# ministm32.net
KiCad netlist of a schematic drawn in EasyEDA Pro
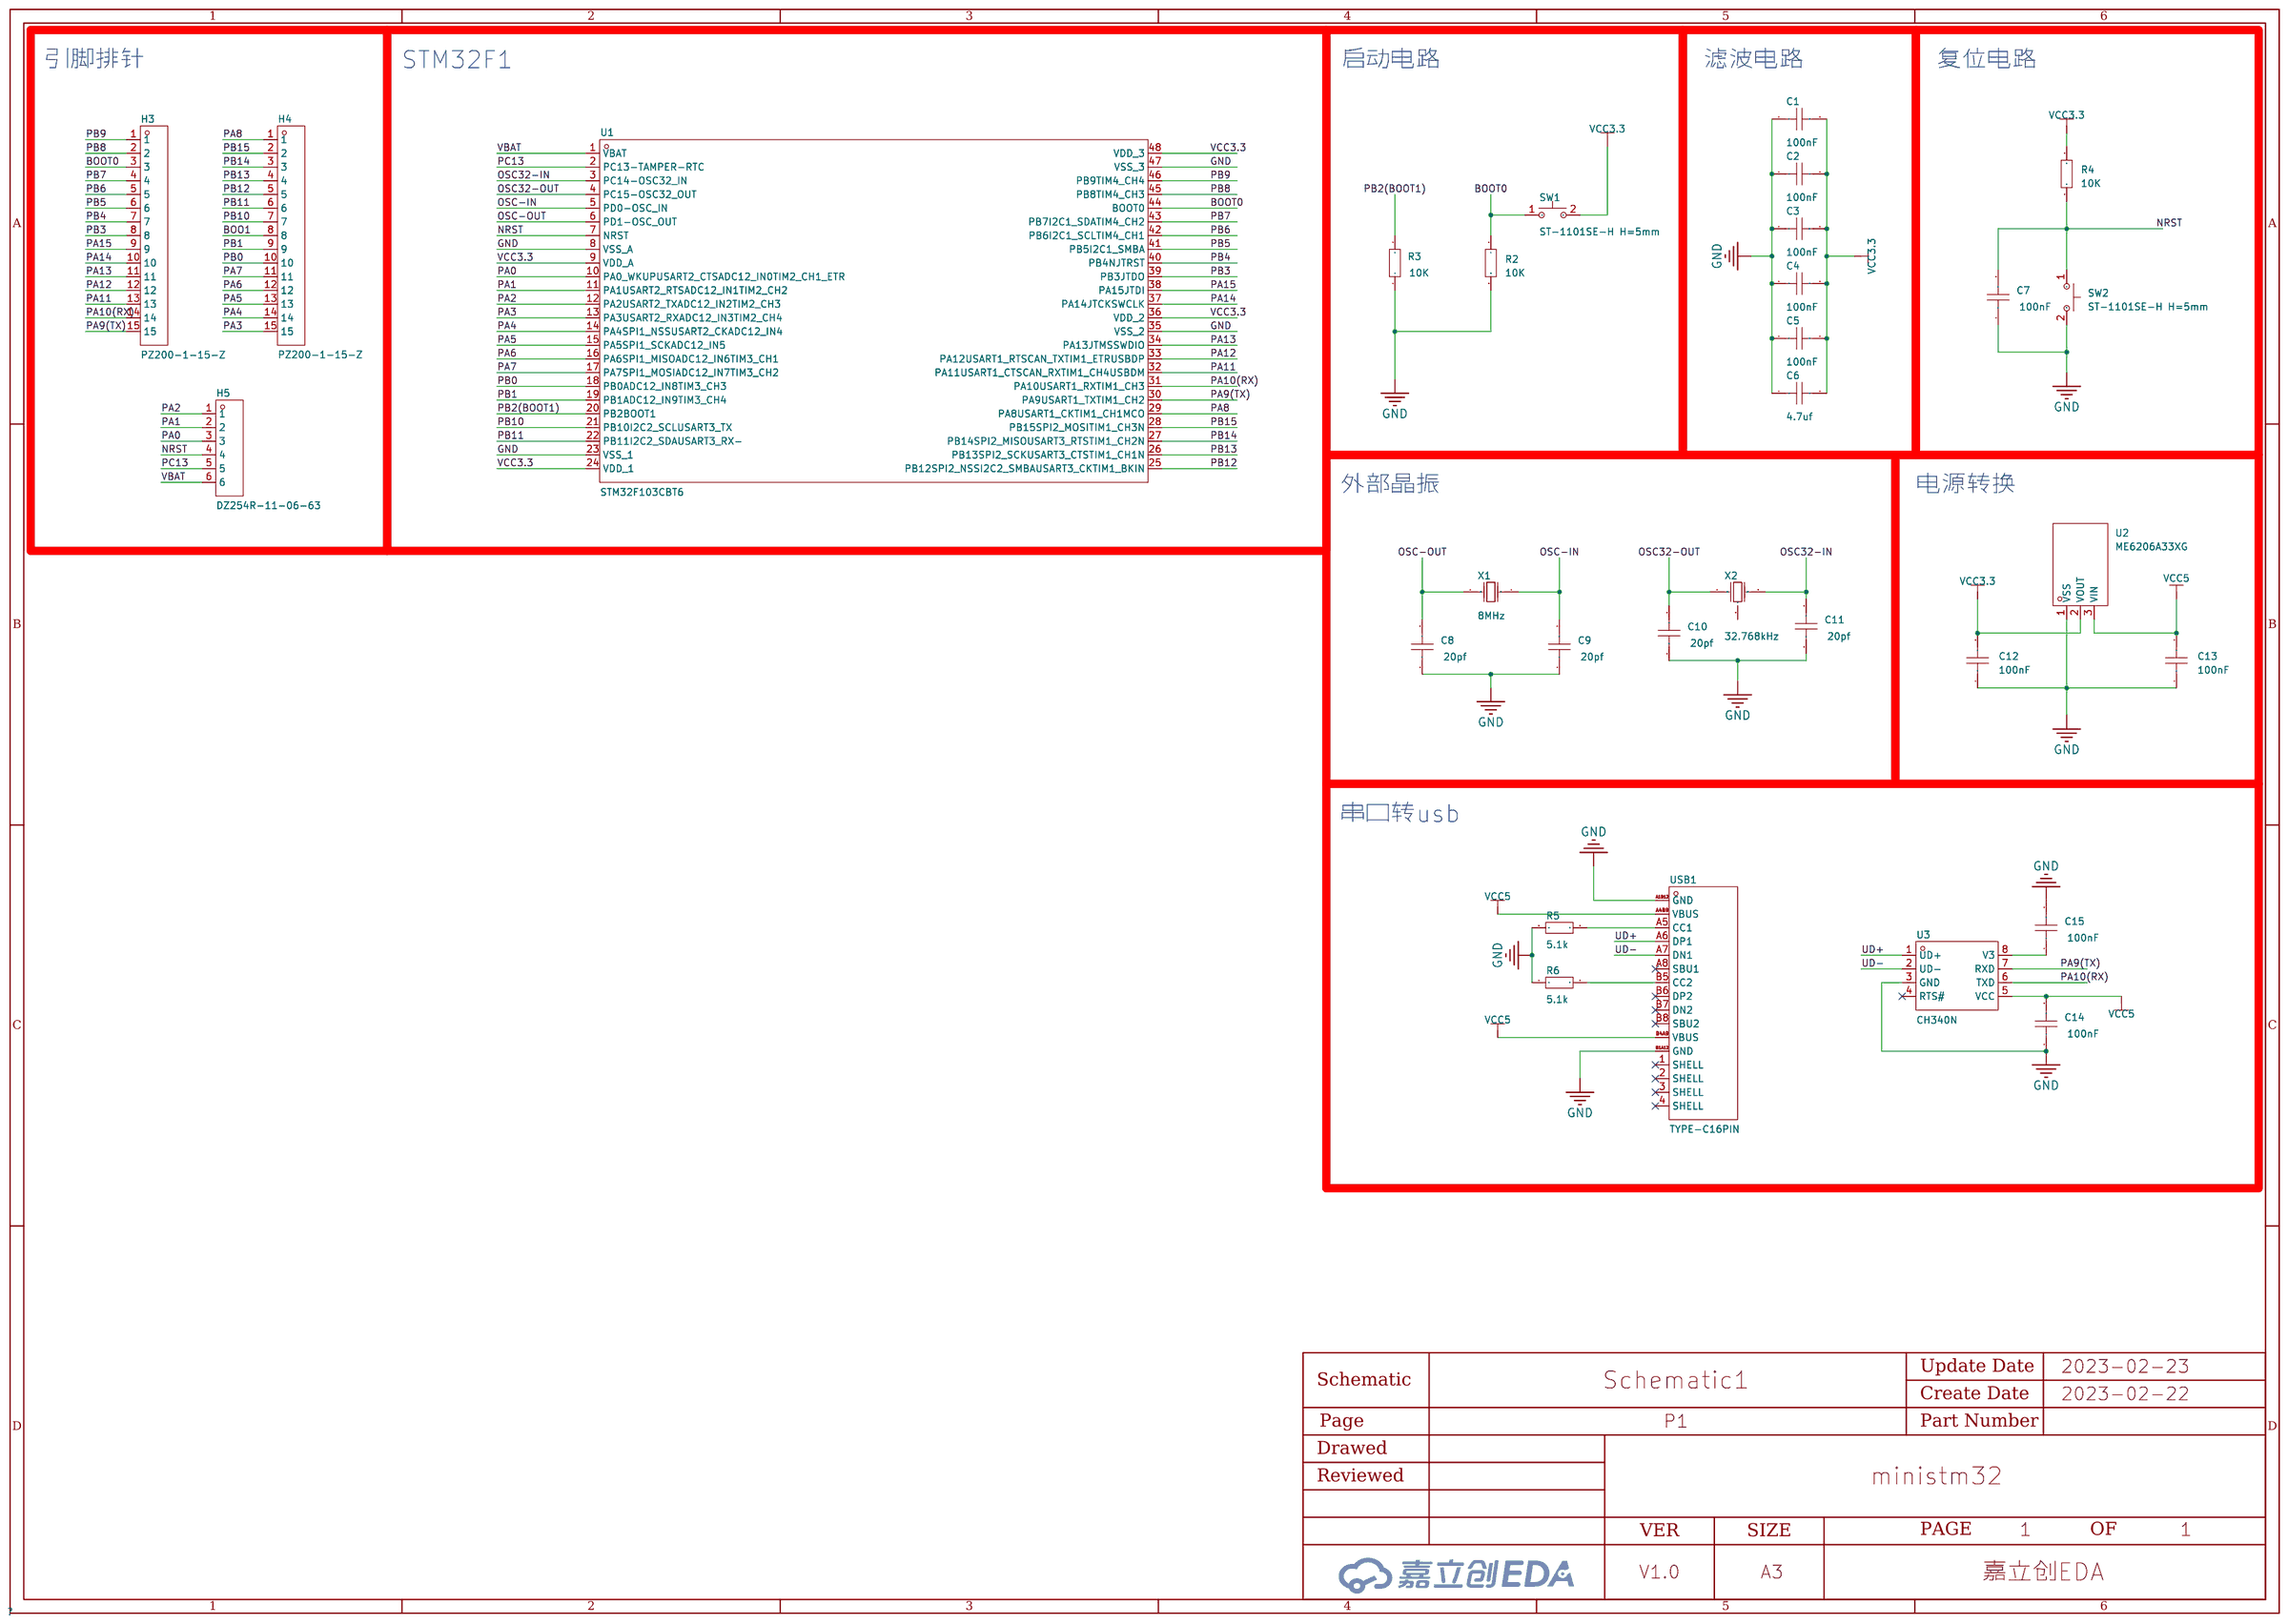
[diagram p0: schematic sheet]

(export (version "E")
  (design (tool "Eeschema 10.0.6"))
  (components
    (comp (ref "C1")
      (value "100nF")
      (footprint "easyedapro:C0603")
      (libsource (lib "easyedapro") (part "CapAcitance"))
    )
    (comp (ref "C2")
      (value "100nF")
      (footprint "easyedapro:C0603")
      (libsource (lib "easyedapro") (part "CapAcitance"))
    )
    (comp (ref "C3")
      (value "100nF")
      (footprint "easyedapro:C0603")
      (libsource (lib "easyedapro") (part "CapAcitance"))
    )
    (comp (ref "C4")
      (value "100nF")
      (footprint "easyedapro:C0603")
      (libsource (lib "easyedapro") (part "CapAcitance"))
    )
    (comp (ref "C5")
      (value "100nF")
      (footprint "easyedapro:C0603")
      (libsource (lib "easyedapro") (part "CapAcitance"))
    )
    (comp (ref "C6")
      (value "4.7uf")
      (footprint "easyedapro:C0603")
      (libsource (lib "easyedapro") (part "CapAcitance"))
    )
    (comp (ref "C7")
      (value "100nF")
      (footprint "easyedapro:C0603")
      (libsource (lib "easyedapro") (part "CapAcitance"))
    )
    (comp (ref "C8")
      (value "20pf")
      (footprint "easyedapro:C0603")
      (libsource (lib "easyedapro") (part "CapAcitance"))
    )
    (comp (ref "C9")
      (value "20pf")
      (footprint "easyedapro:C0603")
      (libsource (lib "easyedapro") (part "CapAcitance"))
    )
    (comp (ref "C10")
      (value "20pf")
      (footprint "easyedapro:C0603")
      (libsource (lib "easyedapro") (part "CapAcitance"))
    )
    (comp (ref "C11")
      (value "20pf")
      (footprint "easyedapro:C0603")
      (libsource (lib "easyedapro") (part "CapAcitance"))
    )
    (comp (ref "C12")
      (value "100nF")
      (footprint "easyedapro:C0603")
      (libsource (lib "easyedapro") (part "CapAcitance"))
    )
    (comp (ref "C13")
      (value "100nF")
      (footprint "easyedapro:C0603")
      (libsource (lib "easyedapro") (part "CapAcitance"))
    )
    (comp (ref "C14")
      (value "100nF")
      (footprint "easyedapro:C0603")
      (libsource (lib "easyedapro") (part "CapAcitance"))
    )
    (comp (ref "C15")
      (value "100nF")
      (footprint "easyedapro:C0603")
      (libsource (lib "easyedapro") (part "CapAcitance"))
    )
    (comp (ref "H3")
      (value "PZ200-1-15-Z")
      (footprint "easyedapro:HDR-TH_15P-P2.00-V-M")
      (fields (field (name "Manufacturer") "HCTL(华灿天禄)"))
      (libsource (lib "easyedapro") (part "PZ200-1-15-Z"))
    )
    (comp (ref "H4")
      (value "PZ200-1-15-Z")
      (footprint "easyedapro:HDR-TH_15P-P2.00-V-M")
      (fields (field (name "Manufacturer") "HCTL(华灿天禄)"))
      (libsource (lib "easyedapro") (part "PZ200-1-15-Z"))
    )
    (comp (ref "H5")
      (value "DZ254R-11-06-63")
      (footprint "easyedapro:HDR-TH_6P-P2.54-V-M")
      (fields (field (name "Manufacturer") "DEALON(德艺隆)"))
      (libsource (lib "easyedapro") (part "DZ254R-11-06-63"))
    )
    (comp (ref "R2") (value "10K") (footprint "easyedapro:R0603") (libsource (lib "easyedapro") (part "电阻")))
    (comp (ref "R3") (value "10K") (footprint "easyedapro:R0603") (libsource (lib "easyedapro") (part "电阻")))
    (comp (ref "R4") (value "10K") (footprint "easyedapro:R0603") (libsource (lib "easyedapro") (part "电阻")))
    (comp (ref "R5") (value "5.1k") (footprint "easyedapro:R0603") (libsource (lib "easyedapro") (part "电阻")))
    (comp (ref "R6") (value "5.1k") (footprint "easyedapro:R0603") (libsource (lib "easyedapro") (part "电阻")))
    (comp (ref "SW1")
      (value "ST-1101SE-H H=5mm")
      (footprint "easyedapro:SW-SMD_L6.1-W3.6-LS8.3-EH")
      (fields (field (name "Manufacturer") "RISHENG(日昇)"))
      (libsource (lib "easyedapro") (part "ST-1101SE-H H=5MM"))
    )
    (comp (ref "SW2")
      (value "ST-1101SE-H H=5mm")
      (footprint "easyedapro:SW-SMD_L6.1-W3.6-LS8.3-EH")
      (fields (field (name "Manufacturer") "RISHENG(日昇)"))
      (libsource (lib "easyedapro") (part "ST-1101SE-H H=5MM"))
    )
    (comp (ref "U1")
      (value "STM32F103CBT6")
      (footprint "easyedapro:LQFP-48_L7.0-W7.0-P0.50-LS9.0-BL")
      (fields (field (name "Manufacturer") "ST(意法半导体)"))
      (libsource (lib "easyedapro") (part "STM32F103CBT6"))
    )
    (comp (ref "U2")
      (value "ME6206A33XG")
      (footprint "easyedapro:SOT-23-3_L2.9-W1.6-P1.90-LS2.8-BR")
      (description "输出类型:固定;输出极性:正;输出通道数:1;最大输入电压:6V;输出电压:3.3V;压差:400mV@(200mA);输出电流:300mA;电源纹波抑制比(PSRR):50dB@(1kHz);")
      (fields (field (name "Manufacturer") "MICRONE(南京微盟)"))
      (libsource (lib "easyedapro") (part "ME6206A33XG"))
    )
    (comp (ref "U3")
      (value "CH340N")
      (footprint "easyedapro:SOP-8_L4.9-W3.9-P1.27-LS6.0-BL")
      (fields (field (name "Manufacturer") "WCH(南京沁恒)"))
      (libsource (lib "easyedapro") (part "CH340N_C2977777"))
    )
    (comp (ref "USB1")
      (value "TYPE-C16PIN")
      (footprint "easyedapro:USB-C-SMD_TYPE-C16PIN")
      (description "连接器类型:Type-C;标准:-;公母:母座;触点数量:16;端口数量:1;安装方式:卧贴;额定电流 - 电源:3A;工作温度范围:-40°C~+85°C;")
      (fields (field (name "Manufacturer") "SHOU HAN(首韩)"))
      (libsource (lib "easyedapro") (part "TYPE-C16PIN"))
    )
    (comp (ref "X1")
      (value "8MHz")
      (footprint "easyedapro:CRYSTAL-SMD_L11.5-W4.8-LS12.7")
      (description "晶振类型:49SMD;频率:8MHz;频率公差:±20ppm;频率稳定度:±30ppm;负载电容:20pF;工作温度:-20°C~+70°C;")
      (fields (field (name "Manufacturer Part") "X49SM8MSD2SC") (field (name "Manufacturer") "YXC(扬兴晶振)"))
      (libsource (lib "easyedapro") (part "X49SM8MSD2SC"))
    )
    (comp (ref "X2")
      (value "32.768kHz")
      (footprint "easyedapro:OSC-SMD_BD2.0-P2.54_TMXLI-206F32.768KHZ12.5PF20PPM")
      (description "晶振类型:贴片无源晶振;频率:32.768kHz;频率公差:±10ppm;负载电容:12.5pF;工作温度:-;")
      (fields
        (field (name "Manufacturer Part") "TAXM32768KBGBAZN2T")
        (field (name "Manufacturer") "TAE(雅晶鑫)")
      )
      (libsource (lib "easyedapro") (part "TMXLI-206F32.768KHZ12PF10PPM"))
    )
  )
  (nets
    (net (code "1") (name "/BOO1") (class "Default")
      (node (ref "H4") (pin "8") (pinfunction "8_8") (pintype "input"))
    )
    (net (code "2") (name "/BOOT0") (class "Default")
      (node (ref "H3") (pin "3") (pinfunction "3_3") (pintype "input"))
      (node (ref "R2") (pin "1") (pinfunction "1_1") (pintype "input"))
      (node (ref "SW1") (pin "1") (pinfunction "1_1") (pintype "input"))
      (node (ref "U1") (pin "44") (pinfunction "BOOT0_44") (pintype "input"))
    )
    (net (code "3") (name "/NRST") (class "Default")
      (node (ref "C7") (pin "2") (pinfunction "2_2") (pintype "input"))
      (node (ref "H5") (pin "4") (pinfunction "4_4") (pintype "input"))
      (node (ref "R4") (pin "1") (pinfunction "1_1") (pintype "input"))
      (node (ref "SW2") (pin "1") (pinfunction "1_1") (pintype "input"))
      (node (ref "U1") (pin "7") (pinfunction "NRST_7") (pintype "input"))
    )
    (net (code "4") (name "/OSC-IN") (class "Default")
      (node (ref "C9") (pin "2") (pinfunction "2_2") (pintype "input"))
      (node (ref "U1") (pin "5") (pinfunction "PD0-OSC_IN_5") (pintype "input"))
      (node (ref "X1") (pin "1") (pinfunction "OSC1_1") (pintype "input"))
    )
    (net (code "5") (name "/OSC-OUT") (class "Default")
      (node (ref "C8") (pin "2") (pinfunction "2_2") (pintype "input"))
      (node (ref "U1") (pin "6") (pinfunction "PD1-OSC_OUT_6") (pintype "input"))
      (node (ref "X1") (pin "2") (pinfunction "OSC2_2") (pintype "input"))
    )
    (net (code "6") (name "/OSC32-IN") (class "Default")
      (node (ref "C11") (pin "2") (pinfunction "2_2") (pintype "input"))
      (node (ref "U1") (pin "3") (pinfunction "PC14-OSC32_IN_3") (pintype "input"))
      (node (ref "X2") (pin "2") (pinfunction "OSC2_2") (pintype "input"))
    )
    (net (code "7") (name "/OSC32-OUT") (class "Default")
      (node (ref "C10") (pin "2") (pinfunction "2_2") (pintype "input"))
      (node (ref "U1") (pin "4") (pinfunction "PC15-OSC32_OUT_4") (pintype "input"))
      (node (ref "X2") (pin "1") (pinfunction "OSC1_1") (pintype "input"))
    )
    (net (code "8") (name "/PA0") (class "Default")
      (node (ref "H5") (pin "3") (pinfunction "3_3") (pintype "input"))
      (node (ref "U1") (pin "10") (pinfunction "PA0_WKUPUSART2_CTSADC12_IN0TIM2_CH1_ETR_10") (pintype "input"))
    )
    (net (code "9") (name "/PA1") (class "Default")
      (node (ref "H5") (pin "2") (pinfunction "2_2") (pintype "input"))
      (node (ref "U1") (pin "11") (pinfunction "PA1USART2_RTSADC12_IN1TIM2_CH2_11") (pintype "input"))
    )
    (net (code "10") (name "/PA2") (class "Default")
      (node (ref "H5") (pin "1") (pinfunction "1_1") (pintype "input"))
      (node (ref "U1") (pin "12") (pinfunction "PA2USART2_TXADC12_IN2TIM2_CH3_12") (pintype "input"))
    )
    (net (code "11") (name "/PA3") (class "Default")
      (node (ref "H4") (pin "15") (pinfunction "15_15") (pintype "input"))
      (node (ref "U1") (pin "13") (pinfunction "PA3USART2_RXADC12_IN3TIM2_CH4_13") (pintype "input"))
    )
    (net (code "12") (name "/PA4") (class "Default")
      (node (ref "H4") (pin "14") (pinfunction "14_14") (pintype "input"))
      (node (ref "U1") (pin "14") (pinfunction "PA4SPI1_NSSUSART2_CKADC12_IN4_14") (pintype "input"))
    )
    (net (code "13") (name "/PA5") (class "Default")
      (node (ref "H4") (pin "13") (pinfunction "13_13") (pintype "input"))
      (node (ref "U1") (pin "15") (pinfunction "PA5SPI1_SCKADC12_IN5_15") (pintype "input"))
    )
    (net (code "14") (name "/PA6") (class "Default")
      (node (ref "H4") (pin "12") (pinfunction "12_12") (pintype "input"))
      (node (ref "U1") (pin "16") (pinfunction "PA6SPI1_MISOADC12_IN6TIM3_CH1_16") (pintype "input"))
    )
    (net (code "15") (name "/PA7") (class "Default")
      (node (ref "H4") (pin "11") (pinfunction "11_11") (pintype "input"))
      (node (ref "U1") (pin "17") (pinfunction "PA7SPI1_MOSIADC12_IN7TIM3_CH2_17") (pintype "input"))
    )
    (net (code "16") (name "/PA8") (class "Default")
      (node (ref "H4") (pin "1") (pinfunction "1_1") (pintype "input"))
      (node (ref "U1") (pin "29") (pinfunction "PA8USART1_CKTIM1_CH1MCO_29") (pintype "input"))
    )
    (net (code "17") (name "/PA9(TX)") (class "Default")
      (node (ref "H3") (pin "15") (pinfunction "15_15") (pintype "input"))
      (node (ref "U1") (pin "30") (pinfunction "PA9USART1_TXTIM1_CH2_30") (pintype "input"))
      (node (ref "U3") (pin "7") (pinfunction "RXD_7") (pintype "input"))
    )
    (net (code "18") (name "/PA10(RX)") (class "Default")
      (node (ref "H3") (pin "14") (pinfunction "14_14") (pintype "input"))
      (node (ref "U1") (pin "31") (pinfunction "PA10USART1_RXTIM1_CH3_31") (pintype "input"))
      (node (ref "U3") (pin "6") (pinfunction "TXD_6") (pintype "input"))
    )
    (net (code "19") (name "/PA11") (class "Default")
      (node (ref "H3") (pin "13") (pinfunction "13_13") (pintype "input"))
      (node (ref "U1") (pin "32") (pinfunction "PA11USART1_CTSCAN_RXTIM1_CH4USBDM_32") (pintype "input"))
    )
    (net (code "20") (name "/PA12") (class "Default")
      (node (ref "H3") (pin "12") (pinfunction "12_12") (pintype "input"))
      (node (ref "U1") (pin "33") (pinfunction "PA12USART1_RTSCAN_TXTIM1_ETRUSBDP_33") (pintype "input"))
    )
    (net (code "21") (name "/PA13") (class "Default")
      (node (ref "H3") (pin "11") (pinfunction "11_11") (pintype "input"))
      (node (ref "U1") (pin "34") (pinfunction "PA13JTMSSWDIO_34") (pintype "input"))
    )
    (net (code "22") (name "/PA14") (class "Default")
      (node (ref "H3") (pin "10") (pinfunction "10_10") (pintype "input"))
      (node (ref "U1") (pin "37") (pinfunction "PA14JTCKSWCLK_37") (pintype "input"))
    )
    (net (code "23") (name "/PA15") (class "Default")
      (node (ref "H3") (pin "9") (pinfunction "9_9") (pintype "input"))
      (node (ref "U1") (pin "38") (pinfunction "PA15JTDI_38") (pintype "input"))
    )
    (net (code "24") (name "/PB0") (class "Default")
      (node (ref "H4") (pin "10") (pinfunction "10_10") (pintype "input"))
      (node (ref "U1") (pin "18") (pinfunction "PB0ADC12_IN8TIM3_CH3_18") (pintype "input"))
    )
    (net (code "25") (name "/PB1") (class "Default")
      (node (ref "H4") (pin "9") (pinfunction "9_9") (pintype "input"))
      (node (ref "U1") (pin "19") (pinfunction "PB1ADC12_IN9TIM3_CH4_19") (pintype "input"))
    )
    (net (code "26") (name "/PB2(BOOT1)") (class "Default")
      (node (ref "R3") (pin "2") (pinfunction "2_2") (pintype "input"))
      (node (ref "U1") (pin "20") (pinfunction "PB2BOOT1_20") (pintype "input"))
    )
    (net (code "27") (name "/PB3") (class "Default")
      (node (ref "H3") (pin "8") (pinfunction "8_8") (pintype "input"))
      (node (ref "U1") (pin "39") (pinfunction "PB3JTDO_39") (pintype "input"))
    )
    (net (code "28") (name "/PB4") (class "Default")
      (node (ref "H3") (pin "7") (pinfunction "7_7") (pintype "input"))
      (node (ref "U1") (pin "40") (pinfunction "PB4NJTRST_40") (pintype "input"))
    )
    (net (code "29") (name "/PB5") (class "Default")
      (node (ref "H3") (pin "6") (pinfunction "6_6") (pintype "input"))
      (node (ref "U1") (pin "41") (pinfunction "PB5I2C1_SMBA_41") (pintype "input"))
    )
    (net (code "30") (name "/PB6") (class "Default")
      (node (ref "H3") (pin "5") (pinfunction "5_5") (pintype "input"))
      (node (ref "U1") (pin "42") (pinfunction "PB6I2C1_SCLTIM4_CH1_42") (pintype "input"))
    )
    (net (code "31") (name "/PB7") (class "Default")
      (node (ref "H3") (pin "4") (pinfunction "4_4") (pintype "input"))
      (node (ref "U1") (pin "43") (pinfunction "PB7I2C1_SDATIM4_CH2_43") (pintype "input"))
    )
    (net (code "32") (name "/PB8") (class "Default")
      (node (ref "H3") (pin "2") (pinfunction "2_2") (pintype "input"))
      (node (ref "U1") (pin "45") (pinfunction "PB8TIM4_CH3_45") (pintype "input"))
    )
    (net (code "33") (name "/PB9") (class "Default")
      (node (ref "H3") (pin "1") (pinfunction "1_1") (pintype "input"))
      (node (ref "U1") (pin "46") (pinfunction "PB9TIM4_CH4_46") (pintype "input"))
    )
    (net (code "34") (name "/PB10") (class "Default")
      (node (ref "H4") (pin "7") (pinfunction "7_7") (pintype "input"))
      (node (ref "U1") (pin "21") (pinfunction "PB10I2C2_SCLUSART3_TX_21") (pintype "input"))
    )
    (net (code "35") (name "/PB11") (class "Default")
      (node (ref "H4") (pin "6") (pinfunction "6_6") (pintype "input"))
      (node (ref "U1") (pin "22") (pinfunction "PB11I2C2_SDAUSART3_RX-_22") (pintype "input"))
    )
    (net (code "36") (name "/PB12") (class "Default")
      (node (ref "H4") (pin "5") (pinfunction "5_5") (pintype "input"))
      (node (ref "U1") (pin "25") (pinfunction "PB12SPI2_NSSI2C2_SMBAUSART3_CKTIM1_BKIN_25") (pintype "input"))
    )
    (net (code "37") (name "/PB13") (class "Default")
      (node (ref "H4") (pin "4") (pinfunction "4_4") (pintype "input"))
      (node (ref "U1") (pin "26") (pinfunction "PB13SPI2_SCKUSART3_CTSTIM1_CH1N_26") (pintype "input"))
    )
    (net (code "38") (name "/PB14") (class "Default")
      (node (ref "H4") (pin "3") (pinfunction "3_3") (pintype "input"))
      (node (ref "U1") (pin "27") (pinfunction "PB14SPI2_MISOUSART3_RTSTIM1_CH2N_27") (pintype "input"))
    )
    (net (code "39") (name "/PB15") (class "Default")
      (node (ref "H4") (pin "2") (pinfunction "2_2") (pintype "input"))
      (node (ref "U1") (pin "28") (pinfunction "PB15SPI2_MOSITIM1_CH3N_28") (pintype "input"))
    )
    (net (code "40") (name "/PC13") (class "Default")
      (node (ref "H5") (pin "5") (pinfunction "5_5") (pintype "input"))
      (node (ref "U1") (pin "2") (pinfunction "PC13-TAMPER-RTC_2") (pintype "input"))
    )
    (net (code "41") (name "/UD+") (class "Default")
      (node (ref "U3") (pin "1") (pinfunction "UD+_1") (pintype "input"))
      (node (ref "USB1") (pin "A6") (pinfunction "DP1_A6") (pintype "input"))
    )
    (net (code "42") (name "/UD-") (class "Default")
      (node (ref "U3") (pin "2") (pinfunction "UD-_2") (pintype "input"))
      (node (ref "USB1") (pin "A7") (pinfunction "DN1_A7") (pintype "input"))
    )
    (net (code "43") (name "/VBAT") (class "Default")
      (node (ref "H5") (pin "6") (pinfunction "6_6") (pintype "input"))
      (node (ref "U1") (pin "1") (pinfunction "VBAT_1") (pintype "input"))
    )
    (net (code "44") (name "GND") (class "Default")
      (node (ref "C1") (pin "1") (pinfunction "1_1") (pintype "input"))
      (node (ref "C10") (pin "1") (pinfunction "1_1") (pintype "input"))
      (node (ref "C11") (pin "1") (pinfunction "1_1") (pintype "input"))
      (node (ref "C12") (pin "1") (pinfunction "1_1") (pintype "input"))
      (node (ref "C13") (pin "1") (pinfunction "1_1") (pintype "input"))
      (node (ref "C14") (pin "1") (pinfunction "1_1") (pintype "input"))
      (node (ref "C15") (pin "2") (pinfunction "2_2") (pintype "input"))
      (node (ref "C2") (pin "1") (pinfunction "1_1") (pintype "input"))
      (node (ref "C3") (pin "1") (pinfunction "1_1") (pintype "input"))
      (node (ref "C4") (pin "1") (pinfunction "1_1") (pintype "input"))
      (node (ref "C5") (pin "1") (pinfunction "1_1") (pintype "input"))
      (node (ref "C6") (pin "1") (pinfunction "1_1") (pintype "input"))
      (node (ref "C7") (pin "1") (pinfunction "1_1") (pintype "input"))
      (node (ref "C8") (pin "1") (pinfunction "1_1") (pintype "input"))
      (node (ref "C9") (pin "1") (pinfunction "1_1") (pintype "input"))
      (node (ref "R2") (pin "2") (pinfunction "2_2") (pintype "input"))
      (node (ref "R3") (pin "1") (pinfunction "1_1") (pintype "input"))
      (node (ref "R5") (pin "1") (pinfunction "1_1") (pintype "input"))
      (node (ref "R6") (pin "1") (pinfunction "1_1") (pintype "input"))
      (node (ref "SW2") (pin "2") (pinfunction "2_2") (pintype "input"))
      (node (ref "U1") (pin "23") (pinfunction "VSS_1_23") (pintype "input"))
      (node (ref "U1") (pin "35") (pinfunction "VSS_2_35") (pintype "input"))
      (node (ref "U1") (pin "47") (pinfunction "VSS_3_47") (pintype "input"))
      (node (ref "U1") (pin "8") (pinfunction "VSS_A_8") (pintype "input"))
      (node (ref "U2") (pin "1") (pinfunction "VSS_1") (pintype "input"))
      (node (ref "U3") (pin "3") (pinfunction "GND_3") (pintype "input"))
      (node (ref "USB1") (pin "A1B12") (pinfunction "GND_A1B12") (pintype "input"))
      (node (ref "USB1") (pin "B1A12") (pinfunction "GND_B1A12") (pintype "input"))
    )
    (net (code "45") (name "Net-(U3-V3)") (class "Default")
      (node (ref "C15") (pin "1") (pinfunction "1_1") (pintype "input"))
      (node (ref "U3") (pin "8") (pinfunction "V3_8") (pintype "input"))
    )
    (net (code "46") (name "Net-(USB1-CC1)") (class "Default")
      (node (ref "R5") (pin "2") (pinfunction "2_2") (pintype "input"))
      (node (ref "USB1") (pin "A5") (pinfunction "CC1_A5") (pintype "input"))
    )
    (net (code "47") (name "Net-(USB1-CC2)") (class "Default")
      (node (ref "R6") (pin "2") (pinfunction "2_2") (pintype "input"))
      (node (ref "USB1") (pin "B5") (pinfunction "CC2_B5") (pintype "input"))
    )
    (net (code "48") (name "VCC3.3") (class "Default")
      (node (ref "C1") (pin "2") (pinfunction "2_2") (pintype "input"))
      (node (ref "C12") (pin "2") (pinfunction "2_2") (pintype "input"))
      (node (ref "C2") (pin "2") (pinfunction "2_2") (pintype "input"))
      (node (ref "C3") (pin "2") (pinfunction "2_2") (pintype "input"))
      (node (ref "C4") (pin "2") (pinfunction "2_2") (pintype "input"))
      (node (ref "C5") (pin "2") (pinfunction "2_2") (pintype "input"))
      (node (ref "C6") (pin "2") (pinfunction "2_2") (pintype "input"))
      (node (ref "R4") (pin "2") (pinfunction "2_2") (pintype "input"))
      (node (ref "SW1") (pin "2") (pinfunction "2_2") (pintype "input"))
      (node (ref "U1") (pin "24") (pinfunction "VDD_1_24") (pintype "input"))
      (node (ref "U1") (pin "36") (pinfunction "VDD_2_36") (pintype "input"))
      (node (ref "U1") (pin "48") (pinfunction "VDD_3_48") (pintype "input"))
      (node (ref "U1") (pin "9") (pinfunction "VDD_A_9") (pintype "input"))
      (node (ref "U2") (pin "2") (pinfunction "VOUT_2") (pintype "input"))
    )
    (net (code "49") (name "VCC5") (class "Default")
      (node (ref "C13") (pin "2") (pinfunction "2_2") (pintype "input"))
      (node (ref "C14") (pin "2") (pinfunction "2_2") (pintype "input"))
      (node (ref "U2") (pin "3") (pinfunction "VIN_3") (pintype "input"))
      (node (ref "U3") (pin "5") (pinfunction "VCC_5") (pintype "input"))
      (node (ref "USB1") (pin "A4B9") (pinfunction "VBUS_A4B9") (pintype "input"))
      (node (ref "USB1") (pin "B4A9") (pinfunction "VBUS_B4A9") (pintype "input"))
    )
    (net (code "50") (name "unconnected-(U3-RTS#-Pad4)") (class "Default")
      (node (ref "U3") (pin "4") (pinfunction "RTS#_4") (pintype "input+no_connect"))
    )
    (net (code "51") (name "unconnected-(USB1-DN2-PadB7)") (class "Default")
      (node (ref "USB1") (pin "B7") (pinfunction "DN2_B7") (pintype "input+no_connect"))
    )
    (net (code "52") (name "unconnected-(USB1-DP2-PadB6)") (class "Default")
      (node (ref "USB1") (pin "B6") (pinfunction "DP2_B6") (pintype "input+no_connect"))
    )
    (net (code "53") (name "unconnected-(USB1-SBU1-PadA8)") (class "Default")
      (node (ref "USB1") (pin "A8") (pinfunction "SBU1_A8") (pintype "input+no_connect"))
    )
    (net (code "54") (name "unconnected-(USB1-SBU2-PadB8)") (class "Default")
      (node (ref "USB1") (pin "B8") (pinfunction "SBU2_B8") (pintype "input+no_connect"))
    )
    (net (code "55") (name "unconnected-(USB1-SHELL-Pad1)") (class "Default")
      (node (ref "USB1") (pin "1") (pinfunction "SHELL_1") (pintype "input+no_connect"))
    )
    (net (code "56") (name "unconnected-(USB1-SHELL-Pad2)") (class "Default")
      (node (ref "USB1") (pin "2") (pinfunction "SHELL_2") (pintype "input+no_connect"))
    )
    (net (code "57") (name "unconnected-(USB1-SHELL-Pad3)") (class "Default")
      (node (ref "USB1") (pin "3") (pinfunction "SHELL_3") (pintype "input+no_connect"))
    )
    (net (code "58") (name "unconnected-(USB1-SHELL-Pad4)") (class "Default")
      (node (ref "USB1") (pin "4") (pinfunction "SHELL_4") (pintype "input+no_connect"))
    )
    (net (code "59") (name "unconnected-(X2-Pad3)") (class "Default")
      (node (ref "X2") (pin "3") (pinfunction "3_3") (pintype "input"))
    )
  )
)
